# 2019_Dashboard.net
KiCad netlist of a schematic drawn in EAGLE
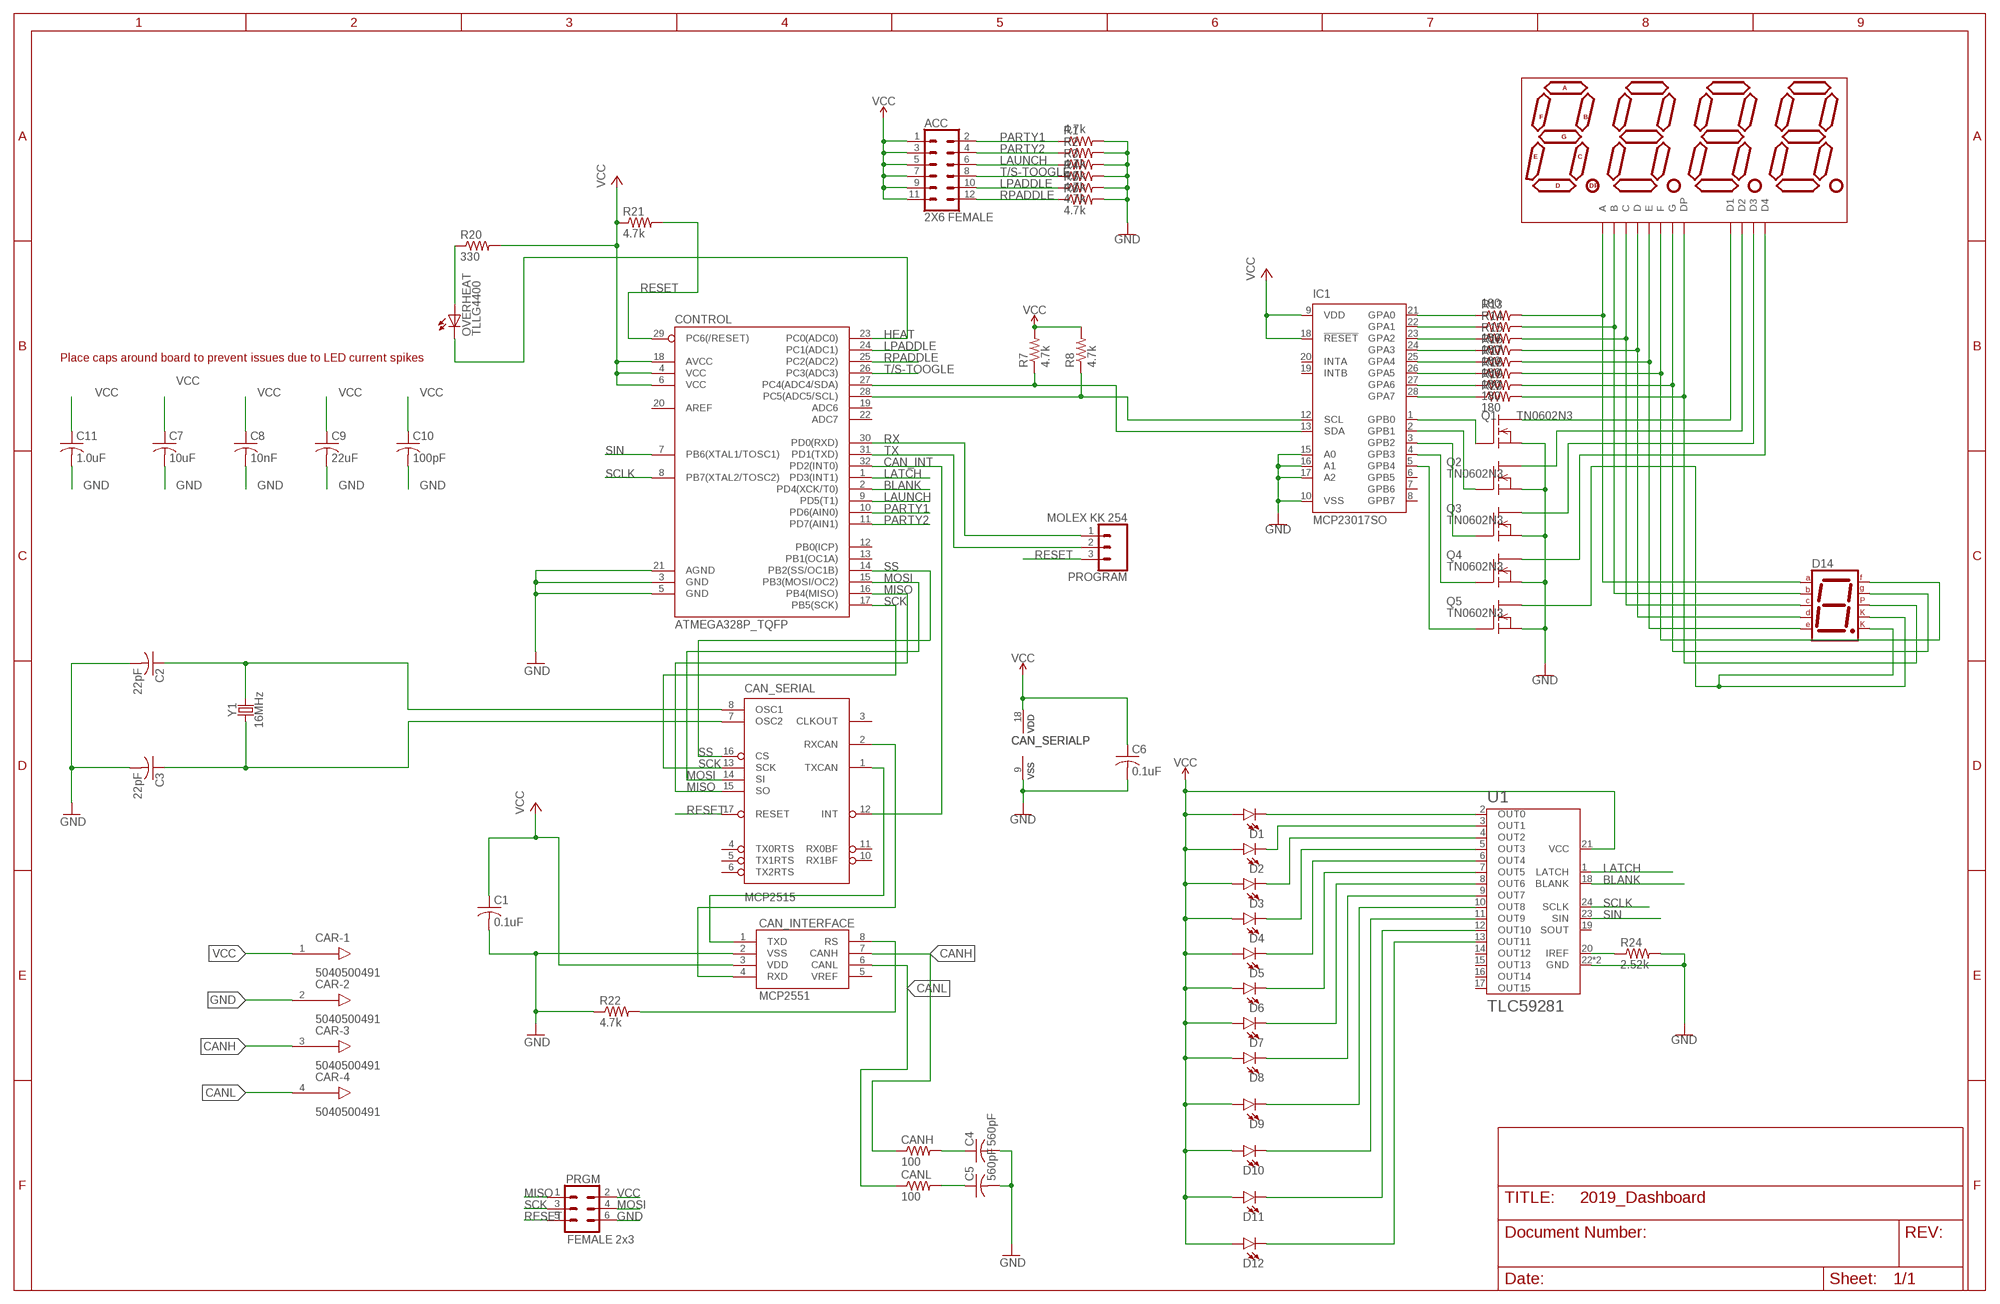
[diagram p0: schematic, sheet 1]

(export (version "E")
  (design (tool "Eeschema 10.0.6"))
  (components
    (comp (ref "ACC")
      (value "2X6 FEMALE")
      (footprint "eagle-import:2X6")
      (libsource (lib "eagle-import") (part "CONN_06X2PTH_FEMALE"))
    )
    (comp (ref "C1")
      (value "0.1uF")
      (footprint "eagle-import:C0603")
      (libsource (lib "eagle-import") (part "C-USC0603"))
    )
    (comp (ref "C2")
      (value "22pF")
      (footprint "eagle-import:C0603")
      (libsource (lib "eagle-import") (part "C-USC0603"))
    )
    (comp (ref "C3")
      (value "22pF")
      (footprint "eagle-import:C0603")
      (libsource (lib "eagle-import") (part "C-USC0603"))
    )
    (comp (ref "C4")
      (value "560pF")
      (footprint "eagle-import:C0603")
      (libsource (lib "eagle-import") (part "C-USC0603"))
    )
    (comp (ref "C5")
      (value "560pF")
      (footprint "eagle-import:C0603")
      (libsource (lib "eagle-import") (part "C-USC0603"))
    )
    (comp (ref "C6")
      (value "0.1uF")
      (footprint "eagle-import:C0603")
      (libsource (lib "eagle-import") (part "C-USC0603"))
    )
    (comp (ref "C7")
      (value "10uF")
      (footprint "eagle-import:C0603")
      (libsource (lib "eagle-import") (part "C-USC0603"))
    )
    (comp (ref "C8")
      (value "10nF")
      (footprint "eagle-import:C0603")
      (libsource (lib "eagle-import") (part "C-USC0603"))
    )
    (comp (ref "C9")
      (value "22uF")
      (footprint "eagle-import:C0603")
      (libsource (lib "eagle-import") (part "C-USC0603"))
    )
    (comp (ref "C10")
      (value "100pF")
      (footprint "eagle-import:C0603")
      (libsource (lib "eagle-import") (part "C-USC0603"))
    )
    (comp (ref "C11")
      (value "1.0uF")
      (footprint "eagle-import:C0603")
      (libsource (lib "eagle-import") (part "C-USC0603"))
    )
    (comp (ref "CANH")
      (value "100")
      (footprint "eagle-import:R0603")
      (libsource (lib "eagle-import") (part "R-US_R0603"))
    )
    (comp (ref "CANL")
      (value "100")
      (footprint "eagle-import:R0603")
      (libsource (lib "eagle-import") (part "R-US_R0603"))
    )
    (comp (ref "CAN_INTERFACE")
      (value "MCP2551")
      (footprint "eagle-import:SO08")
      (libsource (lib "eagle-import") (part "MCP2551"))
    )
    (comp (ref "CAN_SERIAL")
      (value "MCP2515")
      (footprint "eagle-import:SO18W")
      (libsource (lib "eagle-import") (part "MCP2515(MCP2510)SO"))
    )
    (comp (ref "CAR")
      (value "5040500491")
      (footprint "eagle-import:PICOLOCK505050-0491")
      (fields (field (name "MANUFACTURER") "Molex Inc"))
      (libsource (lib "eagle-import") (part "5040500491"))
    )
    (comp (ref "CONTROL")
      (value "ATMEGA328P_TQFP")
      (footprint "eagle-import:TQFP32-08")
      (libsource (lib "eagle-import") (part "ATMEGA328P_TQFP"))
    )
    (comp (ref "D1")
      (value "LED5MM")
      (footprint "eagle-import:LED_5MM")
      (libsource (lib "eagle-import") (part "LED5MM"))
    )
    (comp (ref "D2")
      (value "LED5MM")
      (footprint "eagle-import:LED_5MM")
      (libsource (lib "eagle-import") (part "LED5MM"))
    )
    (comp (ref "D3")
      (value "LED5MM")
      (footprint "eagle-import:LED_5MM")
      (libsource (lib "eagle-import") (part "LED5MM"))
    )
    (comp (ref "D4")
      (value "LED5MM")
      (footprint "eagle-import:LED_5MM")
      (libsource (lib "eagle-import") (part "LED5MM"))
    )
    (comp (ref "D5")
      (value "LED5MM")
      (footprint "eagle-import:LED_5MM")
      (libsource (lib "eagle-import") (part "LED5MM"))
    )
    (comp (ref "D6")
      (value "LED5MM")
      (footprint "eagle-import:LED_5MM")
      (libsource (lib "eagle-import") (part "LED5MM"))
    )
    (comp (ref "D7")
      (value "LED5MM")
      (footprint "eagle-import:LED_5MM")
      (libsource (lib "eagle-import") (part "LED5MM"))
    )
    (comp (ref "D8")
      (value "LED5MM")
      (footprint "eagle-import:LED_5MM")
      (libsource (lib "eagle-import") (part "LED5MM"))
    )
    (comp (ref "D9")
      (value "LED5MM")
      (footprint "eagle-import:LED_5MM")
      (libsource (lib "eagle-import") (part "LED5MM"))
    )
    (comp (ref "D10")
      (value "LED5MM")
      (footprint "eagle-import:LED_5MM")
      (libsource (lib "eagle-import") (part "LED5MM"))
    )
    (comp (ref "D11")
      (value "LED5MM")
      (footprint "eagle-import:LED_5MM")
      (libsource (lib "eagle-import") (part "LED5MM"))
    )
    (comp (ref "D12")
      (value "LED5MM")
      (footprint "eagle-import:LED_5MM")
      (libsource (lib "eagle-import") (part "LED5MM"))
    )
    (comp (ref "D14")
      (value "7SEG-CK")
      (footprint "eagle-import:7SEG-13")
      (libsource (lib "eagle-import") (part "7SEG-CK"))
    )
    (comp (ref "DISP1")
      (value "ATA8041ARBJ")
      (footprint "eagle-import:7-SEGMENT-4DIGIT-20MM")
      (libsource (lib "eagle-import") (part "7-SEGMENT-4DIGIT-20MM-RED"))
    )
    (comp (ref "IC1")
      (value "MCP23017SO")
      (footprint "eagle-import:SO28W")
      (libsource (lib "eagle-import") (part "MCP23017SO"))
    )
    (comp (ref "OVERHEAT")
      (value "TLLG4400")
      (footprint "eagle-import:LED3MM")
      (fields (field (name "MF") "VISHAY SEMICONDUCTOR"))
      (libsource (lib "eagle-import") (part "TLLG4400"))
    )
    (comp (ref "PRGM")
      (value "FEMALE 2x3")
      (footprint "eagle-import:2X3")
      (libsource (lib "eagle-import") (part "CONN_03X2FEMALE"))
    )
    (comp (ref "PROGRAM")
      (value "MOLEX KK 254")
      (footprint "eagle-import:1X03")
      (libsource (lib "eagle-import") (part "CONN_03"))
    )
    (comp (ref "Q1")
      (value "TN0602N3")
      (footprint "eagle-import:TO-92")
      (libsource (lib "eagle-import") (part "TN0602N3"))
    )
    (comp (ref "Q2")
      (value "TN0602N3")
      (footprint "eagle-import:TO-92")
      (libsource (lib "eagle-import") (part "TN0602N3"))
    )
    (comp (ref "Q3")
      (value "TN0602N3")
      (footprint "eagle-import:TO-92")
      (libsource (lib "eagle-import") (part "TN0602N3"))
    )
    (comp (ref "Q4")
      (value "TN0602N3")
      (footprint "eagle-import:TO-92")
      (libsource (lib "eagle-import") (part "TN0602N3"))
    )
    (comp (ref "Q5")
      (value "TN0602N3")
      (footprint "eagle-import:TO-92")
      (libsource (lib "eagle-import") (part "TN0602N3"))
    )
    (comp (ref "R1")
      (value "4.7k")
      (footprint "eagle-import:R0603")
      (libsource (lib "eagle-import") (part "R-US_R0603"))
    )
    (comp (ref "R2")
      (value "4.7k")
      (footprint "eagle-import:R0603")
      (libsource (lib "eagle-import") (part "R-US_R0603"))
    )
    (comp (ref "R3")
      (value "4.7k")
      (footprint "eagle-import:R0603")
      (libsource (lib "eagle-import") (part "R-US_R0603"))
    )
    (comp (ref "R4")
      (value "4.7k")
      (footprint "eagle-import:R0603")
      (libsource (lib "eagle-import") (part "R-US_R0603"))
    )
    (comp (ref "R5")
      (value "4.7k")
      (footprint "eagle-import:R0603")
      (libsource (lib "eagle-import") (part "R-US_R0603"))
    )
    (comp (ref "R6")
      (value "4.7k")
      (footprint "eagle-import:R0603")
      (libsource (lib "eagle-import") (part "R-US_R0603"))
    )
    (comp (ref "R7")
      (value "4.7k")
      (footprint "eagle-import:R0603")
      (libsource (lib "eagle-import") (part "R-US_R0603"))
    )
    (comp (ref "R8")
      (value "4.7k")
      (footprint "eagle-import:R0603")
      (libsource (lib "eagle-import") (part "R-US_R0603"))
    )
    (comp (ref "R13")
      (value "180")
      (footprint "eagle-import:R0603")
      (libsource (lib "eagle-import") (part "R-US_R0603"))
    )
    (comp (ref "R14")
      (value "180")
      (footprint "eagle-import:R0603")
      (libsource (lib "eagle-import") (part "R-US_R0603"))
    )
    (comp (ref "R15")
      (value "180\\")
      (footprint "eagle-import:R0603")
      (libsource (lib "eagle-import") (part "R-US_R0603"))
    )
    (comp (ref "R16")
      (value "180")
      (footprint "eagle-import:R0603")
      (libsource (lib "eagle-import") (part "R-US_R0603"))
    )
    (comp (ref "R17")
      (value "180")
      (footprint "eagle-import:R0603")
      (libsource (lib "eagle-import") (part "R-US_R0603"))
    )
    (comp (ref "R18")
      (value "180")
      (footprint "eagle-import:R0603")
      (libsource (lib "eagle-import") (part "R-US_R0603"))
    )
    (comp (ref "R19")
      (value "180")
      (footprint "eagle-import:R0603")
      (libsource (lib "eagle-import") (part "R-US_R0603"))
    )
    (comp (ref "R20")
      (value "330")
      (footprint "eagle-import:R0603")
      (libsource (lib "eagle-import") (part "R-US_R0603"))
    )
    (comp (ref "R21")
      (value "4.7k")
      (footprint "eagle-import:R0603")
      (libsource (lib "eagle-import") (part "R-US_R0603"))
    )
    (comp (ref "R22")
      (value "4.7k")
      (footprint "eagle-import:R0603")
      (libsource (lib "eagle-import") (part "R-US_R0603"))
    )
    (comp (ref "R23")
      (value "180")
      (footprint "eagle-import:R0603")
      (libsource (lib "eagle-import") (part "R-US_R0603"))
    )
    (comp (ref "R24")
      (value "2.52k")
      (footprint "eagle-import:R0603")
      (libsource (lib "eagle-import") (part "R-US_R0603"))
    )
    (comp (ref "U1")
      (value "TLC59281")
      (footprint "eagle-import:QFN-24")
      (fields (field (name "MF") "Texas Instruments"))
      (libsource (lib "eagle-import") (part "TLC59281"))
    )
    (comp (ref "Y1")
      (value "16MHz")
      (footprint "eagle-import:HC49US")
      (libsource (lib "eagle-import") (part "CRYSTAL-16MHZPTH-HC49US"))
    )
  )
  (nets
    (net (code "1") (name "/BLANK") (class "Default")
      (node (ref "CONTROL") (pin "2") (pinfunction "PD4(XCK/T0)_2") (pintype "bidirectional"))
      (node (ref "U1") (pin "18") (pinfunction "BLANK_18") (pintype "bidirectional"))
    )
    (net (code "2") (name "/CAN_INT") (class "Default")
      (node (ref "CAN_SERIAL") (pin "12") (pinfunction "INT_12") (pintype "output"))
      (node (ref "CONTROL") (pin "32") (pinfunction "PD2(INT0)_32") (pintype "bidirectional"))
    )
    (net (code "3") (name "/HEAT") (class "Default")
      (node (ref "CONTROL") (pin "23") (pinfunction "PC0(ADC0)_23") (pintype "bidirectional"))
      (node (ref "OVERHEAT") (pin "K") (pinfunction "C_K") (pintype "passive"))
    )
    (net (code "4") (name "/LATCH") (class "Default")
      (node (ref "CONTROL") (pin "1") (pinfunction "PD3(INT1)_1") (pintype "bidirectional"))
      (node (ref "U1") (pin "1") (pinfunction "LATCH_1") (pintype "bidirectional"))
    )
    (net (code "5") (name "/LAUNCH") (class "Default")
      (node (ref "ACC") (pin "6") (pinfunction "6_6") (pintype "passive"))
      (node (ref "CONTROL") (pin "9") (pinfunction "PD5(T1)_9") (pintype "bidirectional"))
      (node (ref "R3") (pin "1") (pinfunction "1_1") (pintype "passive"))
    )
    (net (code "6") (name "/LPADDLE") (class "Default")
      (node (ref "ACC") (pin "10") (pinfunction "10_10") (pintype "passive"))
      (node (ref "CONTROL") (pin "24") (pinfunction "PC1(ADC1)_24") (pintype "bidirectional"))
      (node (ref "R5") (pin "1") (pinfunction "1_1") (pintype "passive"))
    )
    (net (code "7") (name "/MISO") (class "Default")
      (node (ref "CAN_SERIAL") (pin "15") (pinfunction "SO_15") (pintype "output"))
      (node (ref "CONTROL") (pin "16") (pinfunction "PB4(MISO)_16") (pintype "bidirectional"))
      (node (ref "PRGM") (pin "1") (pinfunction "1_1") (pintype "bidirectional"))
    )
    (net (code "8") (name "/MOSI") (class "Default")
      (node (ref "CAN_SERIAL") (pin "14") (pinfunction "SI_14") (pintype "input"))
      (node (ref "CONTROL") (pin "15") (pinfunction "PB3(MOSI/OC2)_15") (pintype "bidirectional"))
      (node (ref "PRGM") (pin "4") (pinfunction "4_4") (pintype "bidirectional"))
    )
    (net (code "9") (name "/PARTY1") (class "Default")
      (node (ref "ACC") (pin "2") (pinfunction "2_2") (pintype "passive"))
      (node (ref "CONTROL") (pin "10") (pinfunction "PD6(AIN0)_10") (pintype "bidirectional"))
      (node (ref "R1") (pin "1") (pinfunction "1_1") (pintype "passive"))
    )
    (net (code "10") (name "/PARTY2") (class "Default")
      (node (ref "ACC") (pin "4") (pinfunction "4_4") (pintype "passive"))
      (node (ref "CONTROL") (pin "11") (pinfunction "PD7(AIN1)_11") (pintype "bidirectional"))
      (node (ref "R2") (pin "1") (pinfunction "1_1") (pintype "passive"))
    )
    (net (code "11") (name "/RESET") (class "Default")
      (node (ref "CAN_SERIAL") (pin "17") (pinfunction "RESET_17") (pintype "input"))
      (node (ref "CONTROL") (pin "29") (pinfunction "PC6(/RESET)_29") (pintype "bidirectional"))
      (node (ref "PRGM") (pin "5") (pinfunction "5_5") (pintype "bidirectional"))
      (node (ref "PROGRAM") (pin "3") (pinfunction "3_3") (pintype "passive"))
      (node (ref "R21") (pin "2") (pinfunction "2_2") (pintype "passive"))
    )
    (net (code "12") (name "/RPADDLE") (class "Default")
      (node (ref "ACC") (pin "12") (pinfunction "12_12") (pintype "passive"))
      (node (ref "CONTROL") (pin "25") (pinfunction "PC2(ADC2)_25") (pintype "bidirectional"))
      (node (ref "R6") (pin "1") (pinfunction "1_1") (pintype "passive"))
    )
    (net (code "13") (name "/RX") (class "Default")
      (node (ref "CONTROL") (pin "30") (pinfunction "PD0(RXD)_30") (pintype "bidirectional"))
      (node (ref "PROGRAM") (pin "1") (pinfunction "1_1") (pintype "passive"))
    )
    (net (code "14") (name "/SCK") (class "Default")
      (node (ref "CAN_SERIAL") (pin "13") (pinfunction "SCK_13") (pintype "input"))
      (node (ref "CONTROL") (pin "17") (pinfunction "PB5(SCK)_17") (pintype "bidirectional"))
      (node (ref "PRGM") (pin "3") (pinfunction "3_3") (pintype "bidirectional"))
    )
    (net (code "15") (name "/SCLK") (class "Default")
      (node (ref "CONTROL") (pin "8") (pinfunction "PB7(XTAL2/TOSC2)_8") (pintype "bidirectional"))
      (node (ref "U1") (pin "24") (pinfunction "SCLK_24") (pintype "bidirectional"))
    )
    (net (code "16") (name "/SIN") (class "Default")
      (node (ref "CONTROL") (pin "7") (pinfunction "PB6(XTAL1/TOSC1)_7") (pintype "bidirectional"))
      (node (ref "U1") (pin "23") (pinfunction "SIN_23") (pintype "bidirectional"))
    )
    (net (code "17") (name "/SS") (class "Default")
      (node (ref "CAN_SERIAL") (pin "16") (pinfunction "CS_16") (pintype "input"))
      (node (ref "CONTROL") (pin "14") (pinfunction "PB2(SS/OC1B)_14") (pintype "bidirectional"))
    )
    (net (code "18") (name "/TX") (class "Default")
      (node (ref "CONTROL") (pin "31") (pinfunction "PD1(TXD)_31") (pintype "bidirectional"))
      (node (ref "PROGRAM") (pin "2") (pinfunction "2_2") (pintype "passive"))
    )
    (net (code "19") (name "/T{slash}S-TOOGLE") (class "Default")
      (node (ref "ACC") (pin "8") (pinfunction "8_8") (pintype "passive"))
      (node (ref "CONTROL") (pin "26") (pinfunction "PC3(ADC3)_26") (pintype "bidirectional"))
      (node (ref "R4") (pin "1") (pinfunction "1_1") (pintype "passive"))
    )
    (net (code "20") (name "CANH") (class "Default")
      (node (ref "CANH") (pin "1") (pinfunction "1_1") (pintype "passive"))
      (node (ref "CAN_INTERFACE") (pin "7") (pinfunction "CANH_7") (pintype "bidirectional"))
      (node (ref "CAR") (pin "3") (pinfunction "P$1_3") (pintype "bidirectional"))
    )
    (net (code "21") (name "CANL") (class "Default")
      (node (ref "CANL") (pin "1") (pinfunction "1_1") (pintype "passive"))
      (node (ref "CAN_INTERFACE") (pin "6") (pinfunction "CANL_6") (pintype "bidirectional"))
      (node (ref "CAR") (pin "4") (pinfunction "P$1_4") (pintype "bidirectional"))
    )
    (net (code "22") (name "GND") (class "Default")
      (node (ref "C1") (pin "2") (pinfunction "2_2") (pintype "passive"))
      (node (ref "C10") (pin "2") (pinfunction "2_2") (pintype "passive"))
      (node (ref "C11") (pin "2") (pinfunction "2_2") (pintype "passive"))
      (node (ref "C2") (pin "2") (pinfunction "2_2") (pintype "passive"))
      (node (ref "C3") (pin "2") (pinfunction "2_2") (pintype "passive"))
      (node (ref "C4") (pin "2") (pinfunction "2_2") (pintype "passive"))
      (node (ref "C5") (pin "2") (pinfunction "2_2") (pintype "passive"))
      (node (ref "C6") (pin "2") (pinfunction "2_2") (pintype "passive"))
      (node (ref "C7") (pin "2") (pinfunction "2_2") (pintype "passive"))
      (node (ref "C8") (pin "2") (pinfunction "2_2") (pintype "passive"))
      (node (ref "C9") (pin "2") (pinfunction "2_2") (pintype "passive"))
      (node (ref "CAN_INTERFACE") (pin "2") (pinfunction "VSS_2") (pintype "bidirectional"))
      (node (ref "CAN_SERIAL") (pin "9") (pinfunction "VSS_9") (pintype "power_in"))
      (node (ref "CAR") (pin "2") (pinfunction "P$1_2") (pintype "bidirectional"))
      (node (ref "CONTROL") (pin "21") (pinfunction "AGND_21") (pintype "bidirectional"))
      (node (ref "CONTROL") (pin "3") (pinfunction "GND_3") (pintype "bidirectional"))
      (node (ref "CONTROL") (pin "5") (pinfunction "GND_5") (pintype "bidirectional"))
      (node (ref "IC1") (pin "10") (pinfunction "VSS_10") (pintype "power_in"))
      (node (ref "IC1") (pin "15") (pinfunction "A0_15") (pintype "input"))
      (node (ref "IC1") (pin "16") (pinfunction "A1_16") (pintype "input"))
      (node (ref "IC1") (pin "17") (pinfunction "A2_17") (pintype "input"))
      (node (ref "PRGM") (pin "6") (pinfunction "6_6") (pintype "bidirectional"))
      (node (ref "Q1") (pin "1") (pinfunction "S_1") (pintype "passive"))
      (node (ref "Q2") (pin "1") (pinfunction "S_1") (pintype "passive"))
      (node (ref "Q3") (pin "1") (pinfunction "S_1") (pintype "passive"))
      (node (ref "Q4") (pin "1") (pinfunction "S_1") (pintype "passive"))
      (node (ref "Q5") (pin "1") (pinfunction "S_1") (pintype "passive"))
      (node (ref "R1") (pin "2") (pinfunction "2_2") (pintype "passive"))
      (node (ref "R2") (pin "2") (pinfunction "2_2") (pintype "passive"))
      (node (ref "R22") (pin "1") (pinfunction "1_1") (pintype "passive"))
      (node (ref "R24") (pin "2") (pinfunction "2_2") (pintype "passive"))
      (node (ref "R3") (pin "2") (pinfunction "2_2") (pintype "passive"))
      (node (ref "R4") (pin "2") (pinfunction "2_2") (pintype "passive"))
      (node (ref "R5") (pin "2") (pinfunction "2_2") (pintype "passive"))
      (node (ref "R6") (pin "2") (pinfunction "2_2") (pintype "passive"))
      (node (ref "U1") (pin "22") (pinfunction "GND_22") (pintype "bidirectional"))
      (node (ref "U1") (pin "EP") (pinfunction "GND_EP") (pintype "bidirectional"))
    )
    (net (code "23") (name "Net-(C4-Pad1)") (class "Default")
      (node (ref "C4") (pin "1") (pinfunction "1_1") (pintype "passive"))
      (node (ref "CANH") (pin "2") (pinfunction "2_2") (pintype "passive"))
    )
    (net (code "24") (name "Net-(C5-Pad1)") (class "Default")
      (node (ref "C5") (pin "1") (pinfunction "1_1") (pintype "passive"))
      (node (ref "CANL") (pin "2") (pinfunction "2_2") (pintype "passive"))
    )
    (net (code "25") (name "Net-(CAN_INTERFACE-RS)") (class "Default")
      (node (ref "CAN_INTERFACE") (pin "8") (pinfunction "RS_8") (pintype "bidirectional"))
      (node (ref "R22") (pin "2") (pinfunction "2_2") (pintype "passive"))
    )
    (net (code "26") (name "Net-(CAN_INTERFACE-RXD)") (class "Default")
      (node (ref "CAN_INTERFACE") (pin "4") (pinfunction "RXD_4") (pintype "bidirectional"))
      (node (ref "CAN_SERIAL") (pin "2") (pinfunction "RXCAN_2") (pintype "input"))
    )
    (net (code "27") (name "Net-(CAN_INTERFACE-TXD)") (class "Default")
      (node (ref "CAN_INTERFACE") (pin "1") (pinfunction "TXD_1") (pintype "bidirectional"))
      (node (ref "CAN_SERIAL") (pin "1") (pinfunction "TXCAN_1") (pintype "output"))
    )
    (net (code "28") (name "Net-(CAN_SERIALA-OSC1)") (class "Default")
      (node (ref "C2") (pin "1") (pinfunction "1_1") (pintype "passive"))
      (node (ref "CAN_SERIAL") (pin "8") (pinfunction "OSC1_8") (pintype "input"))
      (node (ref "Y1") (pin "2") (pinfunction "2_2") (pintype "passive"))
    )
    (net (code "29") (name "Net-(CAN_SERIALA-OSC2)") (class "Default")
      (node (ref "C3") (pin "1") (pinfunction "1_1") (pintype "passive"))
      (node (ref "CAN_SERIAL") (pin "7") (pinfunction "OSC2_7") (pintype "output"))
      (node (ref "Y1") (pin "1") (pinfunction "1_1") (pintype "passive"))
    )
    (net (code "30") (name "Net-(CONTROL-PC4(ADC4{slash}SDA))") (class "Default")
      (node (ref "CONTROL") (pin "27") (pinfunction "PC4(ADC4/SDA)_27") (pintype "bidirectional"))
      (node (ref "IC1") (pin "13") (pinfunction "SDA_13") (pintype "bidirectional"))
      (node (ref "R7") (pin "1") (pinfunction "1_1") (pintype "passive"))
    )
    (net (code "31") (name "Net-(CONTROL-PC5(ADC5{slash}SCL))") (class "Default")
      (node (ref "CONTROL") (pin "28") (pinfunction "PC5(ADC5/SCL)_28") (pintype "bidirectional"))
      (node (ref "IC1") (pin "12") (pinfunction "SCL_12") (pintype "input"))
      (node (ref "R8") (pin "1") (pinfunction "1_1") (pintype "passive"))
    )
    (net (code "32") (name "Net-(D1-C)") (class "Default")
      (node (ref "D1") (pin "K") (pinfunction "C_K") (pintype "passive"))
      (node (ref "U1") (pin "2") (pinfunction "OUT0_2") (pintype "bidirectional"))
    )
    (net (code "33") (name "Net-(D2-C)") (class "Default")
      (node (ref "D2") (pin "K") (pinfunction "C_K") (pintype "passive"))
      (node (ref "U1") (pin "3") (pinfunction "OUT1_3") (pintype "bidirectional"))
    )
    (net (code "34") (name "Net-(D3-C)") (class "Default")
      (node (ref "D3") (pin "K") (pinfunction "C_K") (pintype "passive"))
      (node (ref "U1") (pin "4") (pinfunction "OUT2_4") (pintype "bidirectional"))
    )
    (net (code "35") (name "Net-(D4-C)") (class "Default")
      (node (ref "D4") (pin "K") (pinfunction "C_K") (pintype "passive"))
      (node (ref "U1") (pin "5") (pinfunction "OUT3_5") (pintype "bidirectional"))
    )
    (net (code "36") (name "Net-(D5-C)") (class "Default")
      (node (ref "D5") (pin "K") (pinfunction "C_K") (pintype "passive"))
      (node (ref "U1") (pin "6") (pinfunction "OUT4_6") (pintype "bidirectional"))
    )
    (net (code "37") (name "Net-(D6-C)") (class "Default")
      (node (ref "D6") (pin "K") (pinfunction "C_K") (pintype "passive"))
      (node (ref "U1") (pin "7") (pinfunction "OUT5_7") (pintype "bidirectional"))
    )
    (net (code "38") (name "Net-(D7-C)") (class "Default")
      (node (ref "D7") (pin "K") (pinfunction "C_K") (pintype "passive"))
      (node (ref "U1") (pin "8") (pinfunction "OUT6_8") (pintype "bidirectional"))
    )
    (net (code "39") (name "Net-(D8-C)") (class "Default")
      (node (ref "D8") (pin "K") (pinfunction "C_K") (pintype "passive"))
      (node (ref "U1") (pin "9") (pinfunction "OUT7_9") (pintype "bidirectional"))
    )
    (net (code "40") (name "Net-(D9-C)") (class "Default")
      (node (ref "D9") (pin "K") (pinfunction "C_K") (pintype "passive"))
      (node (ref "U1") (pin "10") (pinfunction "OUT8_10") (pintype "bidirectional"))
    )
    (net (code "41") (name "Net-(D10-C)") (class "Default")
      (node (ref "D10") (pin "K") (pinfunction "C_K") (pintype "passive"))
      (node (ref "U1") (pin "11") (pinfunction "OUT9_11") (pintype "bidirectional"))
    )
    (net (code "42") (name "Net-(D11-C)") (class "Default")
      (node (ref "D11") (pin "K") (pinfunction "C_K") (pintype "passive"))
      (node (ref "U1") (pin "12") (pinfunction "OUT10_12") (pintype "bidirectional"))
    )
    (net (code "43") (name "Net-(D12-C)") (class "Default")
      (node (ref "D12") (pin "K") (pinfunction "C_K") (pintype "passive"))
      (node (ref "U1") (pin "13") (pinfunction "OUT11_13") (pintype "bidirectional"))
    )
    (net (code "44") (name "Net-(D14-A)") (class "Default")
      (node (ref "D14") (pin "7") (pinfunction "A_7") (pintype "passive"))
      (node (ref "DISP1") (pin "11") (pinfunction "A_11") (pintype "bidirectional"))
      (node (ref "R13") (pin "2") (pinfunction "2_2") (pintype "passive"))
    )
    (net (code "45") (name "Net-(D14-B)") (class "Default")
      (node (ref "D14") (pin "6") (pinfunction "B_6") (pintype "passive"))
      (node (ref "DISP1") (pin "7") (pinfunction "B_7") (pintype "bidirectional"))
      (node (ref "R14") (pin "2") (pinfunction "2_2") (pintype "passive"))
    )
    (net (code "46") (name "Net-(D14-C)") (class "Default")
      (node (ref "D14") (pin "4") (pinfunction "C_4") (pintype "passive"))
      (node (ref "DISP1") (pin "4") (pinfunction "C_4") (pintype "bidirectional"))
      (node (ref "R15") (pin "2") (pinfunction "2_2") (pintype "passive"))
    )
    (net (code "47") (name "Net-(D14-CK1)") (class "Default")
      (node (ref "D14") (pin "3") (pinfunction "CK1_3") (pintype "passive"))
      (node (ref "D14") (pin "8") (pinfunction "CK2_8") (pintype "passive"))
      (node (ref "Q5") (pin "3") (pinfunction "D_3") (pintype "passive"))
    )
    (net (code "48") (name "Net-(D14-D)") (class "Default")
      (node (ref "D14") (pin "2") (pinfunction "D_2") (pintype "passive"))
      (node (ref "DISP1") (pin "2") (pinfunction "D_2") (pintype "bidirectional"))
      (node (ref "R16") (pin "2") (pinfunction "2_2") (pintype "passive"))
    )
    (net (code "49") (name "Net-(D14-DP)") (class "Default")
      (node (ref "D14") (pin "5") (pinfunction "DP_5") (pintype "passive"))
      (node (ref "DISP1") (pin "3") (pinfunction "DP_3") (pintype "bidirectional"))
      (node (ref "R23") (pin "2") (pinfunction "2_2") (pintype "passive"))
    )
    (net (code "50") (name "Net-(D14-E)") (class "Default")
      (node (ref "D14") (pin "1") (pinfunction "E_1") (pintype "passive"))
      (node (ref "DISP1") (pin "1") (pinfunction "E_1") (pintype "bidirectional"))
      (node (ref "R17") (pin "2") (pinfunction "2_2") (pintype "passive"))
    )
    (net (code "51") (name "Net-(D14-F)") (class "Default")
      (node (ref "D14") (pin "9") (pinfunction "F_9") (pintype "passive"))
      (node (ref "DISP1") (pin "10") (pinfunction "F_10") (pintype "bidirectional"))
      (node (ref "R18") (pin "2") (pinfunction "2_2") (pintype "passive"))
    )
    (net (code "52") (name "Net-(D14-G)") (class "Default")
      (node (ref "D14") (pin "10") (pinfunction "G_10") (pintype "passive"))
      (node (ref "DISP1") (pin "5") (pinfunction "G_5") (pintype "bidirectional"))
      (node (ref "R19") (pin "2") (pinfunction "2_2") (pintype "passive"))
    )
    (net (code "53") (name "Net-(DISP1-D1)") (class "Default")
      (node (ref "DISP1") (pin "12") (pinfunction "D1_12") (pintype "bidirectional"))
      (node (ref "Q1") (pin "3") (pinfunction "D_3") (pintype "passive"))
    )
    (net (code "54") (name "Net-(DISP1-D2)") (class "Default")
      (node (ref "DISP1") (pin "9") (pinfunction "D2_9") (pintype "bidirectional"))
      (node (ref "Q2") (pin "3") (pinfunction "D_3") (pintype "passive"))
    )
    (net (code "55") (name "Net-(DISP1-D3)") (class "Default")
      (node (ref "DISP1") (pin "8") (pinfunction "D3_8") (pintype "bidirectional"))
      (node (ref "Q3") (pin "3") (pinfunction "D_3") (pintype "passive"))
    )
    (net (code "56") (name "Net-(DISP1-D4)") (class "Default")
      (node (ref "DISP1") (pin "6") (pinfunction "D4_6") (pintype "bidirectional"))
      (node (ref "Q4") (pin "3") (pinfunction "D_3") (pintype "passive"))
    )
    (net (code "57") (name "Net-(IC1-GPA0)") (class "Default")
      (node (ref "IC1") (pin "21") (pinfunction "GPA0_21") (pintype "bidirectional"))
      (node (ref "R13") (pin "1") (pinfunction "1_1") (pintype "passive"))
    )
    (net (code "58") (name "Net-(IC1-GPA1)") (class "Default")
      (node (ref "IC1") (pin "22") (pinfunction "GPA1_22") (pintype "bidirectional"))
      (node (ref "R14") (pin "1") (pinfunction "1_1") (pintype "passive"))
    )
    (net (code "59") (name "Net-(IC1-GPA2)") (class "Default")
      (node (ref "IC1") (pin "23") (pinfunction "GPA2_23") (pintype "bidirectional"))
      (node (ref "R15") (pin "1") (pinfunction "1_1") (pintype "passive"))
    )
    (net (code "60") (name "Net-(IC1-GPA3)") (class "Default")
      (node (ref "IC1") (pin "24") (pinfunction "GPA3_24") (pintype "bidirectional"))
      (node (ref "R16") (pin "1") (pinfunction "1_1") (pintype "passive"))
    )
    (net (code "61") (name "Net-(IC1-GPA4)") (class "Default")
      (node (ref "IC1") (pin "25") (pinfunction "GPA4_25") (pintype "bidirectional"))
      (node (ref "R17") (pin "1") (pinfunction "1_1") (pintype "passive"))
    )
    (net (code "62") (name "Net-(IC1-GPA5)") (class "Default")
      (node (ref "IC1") (pin "26") (pinfunction "GPA5_26") (pintype "bidirectional"))
      (node (ref "R18") (pin "1") (pinfunction "1_1") (pintype "passive"))
    )
    (net (code "63") (name "Net-(IC1-GPA6)") (class "Default")
      (node (ref "IC1") (pin "27") (pinfunction "GPA6_27") (pintype "bidirectional"))
      (node (ref "R19") (pin "1") (pinfunction "1_1") (pintype "passive"))
    )
    (net (code "64") (name "Net-(IC1-GPA7)") (class "Default")
      (node (ref "IC1") (pin "28") (pinfunction "GPA7_28") (pintype "bidirectional"))
      (node (ref "R23") (pin "1") (pinfunction "1_1") (pintype "passive"))
    )
    (net (code "65") (name "Net-(IC1-GPB0)") (class "Default")
      (node (ref "IC1") (pin "1") (pinfunction "GPB0_1") (pintype "bidirectional"))
      (node (ref "Q1") (pin "2") (pinfunction "G_2") (pintype "passive"))
    )
    (net (code "66") (name "Net-(IC1-GPB1)") (class "Default")
      (node (ref "IC1") (pin "2") (pinfunction "GPB1_2") (pintype "bidirectional"))
      (node (ref "Q2") (pin "2") (pinfunction "G_2") (pintype "passive"))
    )
    (net (code "67") (name "Net-(IC1-GPB2)") (class "Default")
      (node (ref "IC1") (pin "3") (pinfunction "GPB2_3") (pintype "bidirectional"))
      (node (ref "Q3") (pin "2") (pinfunction "G_2") (pintype "passive"))
    )
    (net (code "68") (name "Net-(IC1-GPB3)") (class "Default")
      (node (ref "IC1") (pin "4") (pinfunction "GPB3_4") (pintype "bidirectional"))
      (node (ref "Q4") (pin "2") (pinfunction "G_2") (pintype "passive"))
    )
    (net (code "69") (name "Net-(IC1-GPB4)") (class "Default")
      (node (ref "IC1") (pin "5") (pinfunction "GPB4_5") (pintype "bidirectional"))
      (node (ref "Q5") (pin "2") (pinfunction "G_2") (pintype "passive"))
    )
    (net (code "70") (name "Net-(OVERHEAT-PadA)") (class "Default")
      (node (ref "OVERHEAT") (pin "A") (pinfunction "A_A") (pintype "passive"))
      (node (ref "R20") (pin "1") (pinfunction "1_1") (pintype "passive"))
    )
    (net (code "71") (name "Net-(U1-IREF)") (class "Default")
      (node (ref "R24") (pin "1") (pinfunction "1_1") (pintype "passive"))
      (node (ref "U1") (pin "20") (pinfunction "IREF_20") (pintype "bidirectional"))
    )
    (net (code "72") (name "VCC") (class "Default")
      (node (ref "ACC") (pin "1") (pinfunction "1_1") (pintype "passive"))
      (node (ref "ACC") (pin "11") (pinfunction "11_11") (pintype "passive"))
      (node (ref "ACC") (pin "3") (pinfunction "3_3") (pintype "passive"))
      (node (ref "ACC") (pin "5") (pinfunction "5_5") (pintype "passive"))
      (node (ref "ACC") (pin "7") (pinfunction "7_7") (pintype "passive"))
      (node (ref "ACC") (pin "9") (pinfunction "9_9") (pintype "passive"))
      (node (ref "C1") (pin "1") (pinfunction "1_1") (pintype "passive"))
      (node (ref "C10") (pin "1") (pinfunction "1_1") (pintype "passive"))
      (node (ref "C11") (pin "1") (pinfunction "1_1") (pintype "passive"))
      (node (ref "C6") (pin "1") (pinfunction "1_1") (pintype "passive"))
      (node (ref "C7") (pin "1") (pinfunction "1_1") (pintype "passive"))
      (node (ref "C8") (pin "1") (pinfunction "1_1") (pintype "passive"))
      (node (ref "C9") (pin "1") (pinfunction "1_1") (pintype "passive"))
      (node (ref "CAN_INTERFACE") (pin "3") (pinfunction "VDD_3") (pintype "bidirectional"))
      (node (ref "CAN_SERIAL") (pin "18") (pinfunction "VDD_18") (pintype "power_in"))
      (node (ref "CAR") (pin "1") (pinfunction "P$1_1") (pintype "bidirectional"))
      (node (ref "CONTROL") (pin "18") (pinfunction "AVCC_18") (pintype "bidirectional"))
      (node (ref "CONTROL") (pin "4") (pinfunction "VCC_4") (pintype "bidirectional"))
      (node (ref "CONTROL") (pin "6") (pinfunction "VCC_6") (pintype "bidirectional"))
      (node (ref "D1") (pin "A") (pinfunction "A_A") (pintype "passive"))
      (node (ref "D10") (pin "A") (pinfunction "A_A") (pintype "passive"))
      (node (ref "D11") (pin "A") (pinfunction "A_A") (pintype "passive"))
      (node (ref "D12") (pin "A") (pinfunction "A_A") (pintype "passive"))
      (node (ref "D2") (pin "A") (pinfunction "A_A") (pintype "passive"))
      (node (ref "D3") (pin "A") (pinfunction "A_A") (pintype "passive"))
      (node (ref "D4") (pin "A") (pinfunction "A_A") (pintype "passive"))
      (node (ref "D5") (pin "A") (pinfunction "A_A") (pintype "passive"))
      (node (ref "D6") (pin "A") (pinfunction "A_A") (pintype "passive"))
      (node (ref "D7") (pin "A") (pinfunction "A_A") (pintype "passive"))
      (node (ref "D8") (pin "A") (pinfunction "A_A") (pintype "passive"))
      (node (ref "D9") (pin "A") (pinfunction "A_A") (pintype "passive"))
      (node (ref "IC1") (pin "18") (pinfunction "~{RESET}_18") (pintype "input"))
      (node (ref "IC1") (pin "9") (pinfunction "VDD_9") (pintype "power_in"))
      (node (ref "PRGM") (pin "2") (pinfunction "2_2") (pintype "bidirectional"))
      (node (ref "R20") (pin "2") (pinfunction "2_2") (pintype "passive"))
      (node (ref "R21") (pin "1") (pinfunction "1_1") (pintype "passive"))
      (node (ref "R7") (pin "2") (pinfunction "2_2") (pintype "passive"))
      (node (ref "R8") (pin "2") (pinfunction "2_2") (pintype "passive"))
      (node (ref "U1") (pin "21") (pinfunction "VCC_21") (pintype "bidirectional"))
    )
    (net (code "73") (name "unconnected-(CAN_INTERFACE-VREF-Pad5)") (class "Default")
      (node (ref "CAN_INTERFACE") (pin "5") (pinfunction "VREF_5") (pintype "bidirectional"))
    )
    (net (code "74") (name "unconnected-(CAN_SERIALA-CLKOUT-Pad3)") (class "Default")
      (node (ref "CAN_SERIAL") (pin "3") (pinfunction "CLKOUT_3") (pintype "output"))
    )
    (net (code "75") (name "unconnected-(CAN_SERIALA-RX0BF-Pad11)") (class "Default")
      (node (ref "CAN_SERIAL") (pin "11") (pinfunction "RX0BF_11") (pintype "output"))
    )
    (net (code "76") (name "unconnected-(CAN_SERIALA-RX1BF-Pad10)") (class "Default")
      (node (ref "CAN_SERIAL") (pin "10") (pinfunction "RX1BF_10") (pintype "output"))
    )
    (net (code "77") (name "unconnected-(CAN_SERIALA-TX0RTS-Pad4)") (class "Default")
      (node (ref "CAN_SERIAL") (pin "4") (pinfunction "TX0RTS_4") (pintype "input"))
    )
    (net (code "78") (name "unconnected-(CAN_SERIALA-TX1RTS-Pad5)") (class "Default")
      (node (ref "CAN_SERIAL") (pin "5") (pinfunction "TX1RTS_5") (pintype "input"))
    )
    (net (code "79") (name "unconnected-(CAN_SERIALA-TX2RTS-Pad6)") (class "Default")
      (node (ref "CAN_SERIAL") (pin "6") (pinfunction "TX2RTS_6") (pintype "input"))
    )
    (net (code "80") (name "unconnected-(CONTROL-ADC6-Pad19)") (class "Default")
      (node (ref "CONTROL") (pin "19") (pinfunction "ADC6_19") (pintype "bidirectional"))
    )
    (net (code "81") (name "unconnected-(CONTROL-ADC7-Pad22)") (class "Default")
      (node (ref "CONTROL") (pin "22") (pinfunction "ADC7_22") (pintype "bidirectional"))
    )
    (net (code "82") (name "unconnected-(CONTROL-AREF-Pad20)") (class "Default")
      (node (ref "CONTROL") (pin "20") (pinfunction "AREF_20") (pintype "bidirectional"))
    )
    (net (code "83") (name "unconnected-(CONTROL-PB0(ICP)-Pad12)") (class "Default")
      (node (ref "CONTROL") (pin "12") (pinfunction "PB0(ICP)_12") (pintype "bidirectional"))
    )
    (net (code "84") (name "unconnected-(CONTROL-PB1(OC1A)-Pad13)") (class "Default")
      (node (ref "CONTROL") (pin "13") (pinfunction "PB1(OC1A)_13") (pintype "bidirectional"))
    )
    (net (code "85") (name "unconnected-(IC1-GPB5-Pad6)") (class "Default")
      (node (ref "IC1") (pin "6") (pinfunction "GPB5_6") (pintype "bidirectional"))
    )
    (net (code "86") (name "unconnected-(IC1-GPB6-Pad7)") (class "Default")
      (node (ref "IC1") (pin "7") (pinfunction "GPB6_7") (pintype "bidirectional"))
    )
    (net (code "87") (name "unconnected-(IC1-GPB7-Pad8)") (class "Default")
      (node (ref "IC1") (pin "8") (pinfunction "GPB7_8") (pintype "bidirectional"))
    )
    (net (code "88") (name "unconnected-(IC1-INTA-Pad20)") (class "Default")
      (node (ref "IC1") (pin "20") (pinfunction "INTA_20") (pintype "output"))
    )
    (net (code "89") (name "unconnected-(IC1-INTB-Pad19)") (class "Default")
      (node (ref "IC1") (pin "19") (pinfunction "INTB_19") (pintype "output"))
    )
    (net (code "90") (name "unconnected-(U1-OUT12-Pad14)") (class "Default")
      (node (ref "U1") (pin "14") (pinfunction "OUT12_14") (pintype "bidirectional"))
    )
    (net (code "91") (name "unconnected-(U1-OUT13-Pad15)") (class "Default")
      (node (ref "U1") (pin "15") (pinfunction "OUT13_15") (pintype "bidirectional"))
    )
    (net (code "92") (name "unconnected-(U1-OUT14-Pad16)") (class "Default")
      (node (ref "U1") (pin "16") (pinfunction "OUT14_16") (pintype "bidirectional"))
    )
    (net (code "93") (name "unconnected-(U1-OUT15-Pad17)") (class "Default")
      (node (ref "U1") (pin "17") (pinfunction "OUT15_17") (pintype "bidirectional"))
    )
    (net (code "94") (name "unconnected-(U1-SOUT-Pad19)") (class "Default")
      (node (ref "U1") (pin "19") (pinfunction "SOUT_19") (pintype "bidirectional"))
    )
  )
)
